# 6_Power.net
KiCad netlist of a schematic drawn in Altium Designer
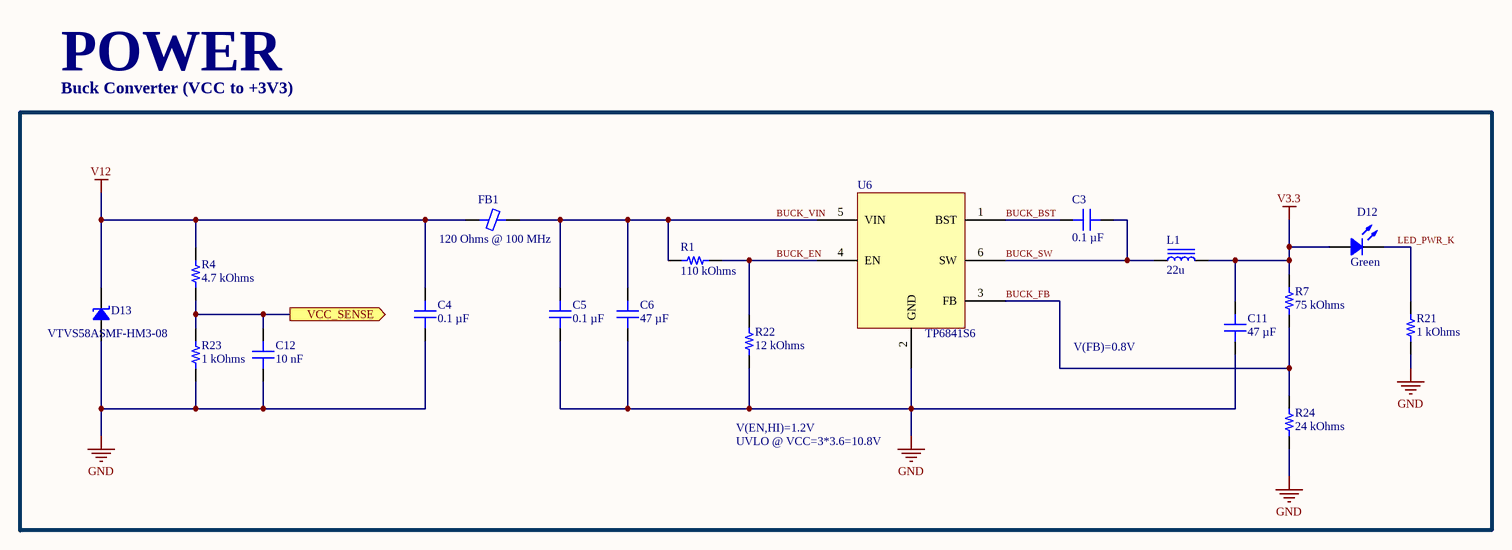
[diagram p0: 6_Power.SchDoc]

(export (version "E")
  (design (tool "Eeschema 10.0.6"))
  (components
    (comp (ref "C3")
      (value "0.1 µF")
      (footprint "CAP 0805_2012")
      (description "CAP CER 0.1UF 50V X7R 0805")
      (fields (field (name "PART NUMBER") "CC0805MRX7R9BB104") (field (name "MANUFACTURER") "Yageo"))
      (libsource (lib "Celestial Altium Library - altium_library") (part "Capacitor"))
    )
    (comp (ref "C4")
      (value "0.1 µF")
      (footprint "CAP 0805_2012")
      (description "CAP CER 0.1UF 50V X7R 0805")
      (fields (field (name "PART NUMBER") "CC0805MRX7R9BB104") (field (name "MANUFACTURER") "Yageo"))
      (libsource (lib "Celestial Altium Library - altium_library") (part "Capacitor"))
    )
    (comp (ref "C5")
      (value "0.1 µF")
      (footprint "CAP 0805_2012")
      (description "CAP CER 0.1UF 50V X7R 0805")
      (fields (field (name "PART NUMBER") "CC0805MRX7R9BB104") (field (name "MANUFACTURER") "Yageo"))
      (libsource (lib "Celestial Altium Library - altium_library") (part "Capacitor"))
    )
    (comp (ref "C6")
      (value "47 µF")
      (footprint "CAP 1210_3225 - 1MM")
      (description "CAP CER 47UF 16V X6S 1210")
      (fields
        (field (name "PART NUMBER") "GRM32EC81C476KE15L")
        (field (name "MANUFACTURER") "Murata Electronics")
      )
      (libsource (lib "Celestial Altium Library - altium_library") (part "Capacitor"))
    )
    (comp (ref "C11")
      (value "47 µF")
      (footprint "CAP 1210_3225 - 1MM")
      (description "CAP CER 47UF 16V X6S 1210")
      (fields
        (field (name "PART NUMBER") "GRM32EC81C476KE15L")
        (field (name "MANUFACTURER") "Murata Electronics")
      )
      (libsource (lib "Celestial Altium Library - altium_library") (part "Capacitor"))
    )
    (comp (ref "C12")
      (value "10 nF")
      (footprint "CAP 0805_2012")
      (description "CAP CER 0805 10NF 100V X7R")
      (fields (field (name "PART NUMBER") "C0805X103K1RAC3316") (field (name "MANUFACTURER") "KEMET"))
      (libsource (lib "Celestial Altium Library - altium_library") (part "Capacitor"))
    )
    (comp (ref "D12")
      (value "Green")
      (footprint "LED 0805_2012 GREEN")
      (description "LED GREEN CLEAR 0805 SMD")
      (fields (field (name "PART NUMBER") "SM0805UGC") (field (name "MANUFACTURER") "Bivar Inc."))
      (libsource (lib "Celestial Altium Library - altium_library") (part "LED"))
    )
    (comp (ref "D13")
      (value "VTVS58ASMF-HM3-08")
      (footprint "SMF DO-219AB")
      (description "TVS DIODE 57.6V 98V DO219AB")
      (fields (field (name "MANUFACTURER") "Vishay Semiconductor Diodes Division"))
      (libsource (lib "Celestial Altium Library - altium_library") (part "DIODE TVS UNI"))
    )
    (comp (ref "FB1")
      (value "120 Ohms @ 100 MHz")
      (footprint "CAP 1812_4532 1.1MM")
      (description "SMT Ferrite Chip")
      (libsource (lib "BLDC_BridgeBoard_V1_2") (part "Ferrite Chip 1812"))
    )
    (comp (ref "L1")
      (value "22u")
      (footprint "Milibreria:INDUCTOR_1R5")
      (description "SMT Inductor")
      (libsource (lib "BLDC_BridgeBoard_V1") (part "Inductor"))
    )
    (comp (ref "R1")
      (value "110 kOhms")
      (footprint "RES 0805_2012")
      (description "RES SMD 110K OHM 1% 1/8W 0805")
      (fields (field (name "PART NUMBER") "CRCW0805110KFKEA") (field (name "MANUFACTURER") "Vishay Dale"))
      (libsource (lib "Celestial Altium Library - altium_library") (part "Resistor"))
    )
    (comp (ref "R4")
      (value "4.7 kOhms")
      (footprint "RES 0805_2012")
      (description "RES SMD 4.7K OHM 5% 1/2W 0805")
      (fields (field (name "PART NUMBER") "RCS08054K70JNEA") (field (name "MANUFACTURER") "Vishay Dale"))
      (libsource (lib "Celestial Altium Library - altium_library") (part "Resistor"))
    )
    (comp (ref "R7")
      (value "75 kOhms")
      (footprint "RES 0805_2012")
      (description "RES SMD 75K OHM 0.5% 1/8W 0805")
      (fields (field (name "PART NUMBER") "RT0805DRD0775KL") (field (name "MANUFACTURER") "Yageo"))
      (libsource (lib "Celestial Altium Library - altium_library") (part "Resistor"))
    )
    (comp (ref "R21")
      (value "1 kOhms")
      (footprint "RES 0805_2012")
      (description "RES SMD 200K OHM 5% 1/8W 0805")
      (fields (field (name "PART NUMBER") "CR0805-JW-204ELF") (field (name "MANUFACTURER") "Bourns Inc."))
      (libsource (lib "Celestial Altium Library - altium_library") (part "Resistor"))
    )
    (comp (ref "R22")
      (value "12 kOhms")
      (footprint "RES 0805_2012")
      (description "RES 12K OHM 1% 1/3W 0805")
      (fields
        (field (name "PART NUMBER") "CRGP0805F12K")
        (field (name "MANUFACTURER") "TE Connectivity Passive Product")
      )
      (libsource (lib "Celestial Altium Library - altium_library") (part "Resistor"))
    )
    (comp (ref "R23")
      (value "1 kOhms")
      (footprint "RES 0805_2012")
      (description "RES SMD 200K OHM 5% 1/8W 0805")
      (fields (field (name "PART NUMBER") "CR0805-JW-204ELF") (field (name "MANUFACTURER") "Bourns Inc."))
      (libsource (lib "Celestial Altium Library - altium_library") (part "Resistor"))
    )
    (comp (ref "R24")
      (value "24 kOhms")
      (footprint "RES 0805_2012")
      (description "RES SMD 24K OHM 1% 1/8W 0805")
      (fields
        (field (name "PART NUMBER") "CRG0805F24K")
        (field (name "MANUFACTURER") "TE Connectivity Passive Product")
      )
      (libsource (lib "Celestial Altium Library - altium_library") (part "Resistor"))
    )
    (comp (ref "U6")
      (value "TP6841S6")
      (footprint "SOT95P280X125-6M")
      (description "TP6841S6 Power Supply. 4.5 to 40 V input voltage. Up to 800 mA output current.")
      (libsource (lib "BLDC_BridgeBoard_V1") (part "TP6841S6"))
    )
  )
  (nets
    (net (code "1") (name "/BUCK_BST") (class "Default")
      (node (ref "C3") (pin "2") (pinfunction "2_2") (pintype "passive"))
      (node (ref "U6") (pin "1") (pinfunction "BST_1") (pintype "passive"))
    )
    (net (code "2") (name "/BUCK_EN") (class "Default")
      (node (ref "R1") (pin "1") (pinfunction "1_1") (pintype "passive"))
      (node (ref "R22") (pin "2") (pinfunction "2_2") (pintype "passive"))
      (node (ref "U6") (pin "4") (pinfunction "EN_4") (pintype "passive"))
    )
    (net (code "3") (name "/BUCK_FB") (class "Default")
      (node (ref "R24") (pin "2") (pinfunction "2_2") (pintype "passive"))
      (node (ref "R7") (pin "1") (pinfunction "1_1") (pintype "passive"))
      (node (ref "U6") (pin "3") (pinfunction "FB_3") (pintype "passive"))
    )
    (net (code "4") (name "/BUCK_SW") (class "Default")
      (node (ref "C3") (pin "1") (pinfunction "1_1") (pintype "passive"))
      (node (ref "L1") (pin "1") (pinfunction "1_1") (pintype "passive"))
      (node (ref "U6") (pin "6") (pinfunction "SW_6") (pintype "passive"))
    )
    (net (code "5") (name "/BUCK_VIN") (class "Default")
      (node (ref "C5") (pin "2") (pinfunction "2_2") (pintype "passive"))
      (node (ref "C6") (pin "2") (pinfunction "2_2") (pintype "passive"))
      (node (ref "FB1") (pin "2") (pinfunction "2_2") (pintype "passive"))
      (node (ref "R1") (pin "2") (pinfunction "2_2") (pintype "passive"))
      (node (ref "U6") (pin "5") (pinfunction "VIN_5") (pintype "passive"))
    )
    (net (code "6") (name "/LED_PWR_K") (class "Default")
      (node (ref "D12") (pin "2") (pinfunction "2_2") (pintype "passive"))
      (node (ref "R21") (pin "2") (pinfunction "2_2") (pintype "passive"))
    )
    (net (code "7") (name "/VCC_SENSE") (class "Default")
      (node (ref "C12") (pin "2") (pinfunction "2_2") (pintype "passive"))
      (node (ref "R23") (pin "2") (pinfunction "2_2") (pintype "passive"))
      (node (ref "R4") (pin "1") (pinfunction "1_1") (pintype "passive"))
    )
    (net (code "8") (name "GND") (class "Default")
      (node (ref "C11") (pin "1") (pinfunction "1_1") (pintype "passive"))
      (node (ref "C12") (pin "1") (pinfunction "1_1") (pintype "passive"))
      (node (ref "C4") (pin "1") (pinfunction "1_1") (pintype "passive"))
      (node (ref "C5") (pin "1") (pinfunction "1_1") (pintype "passive"))
      (node (ref "C6") (pin "1") (pinfunction "1_1") (pintype "passive"))
      (node (ref "D13") (pin "1") (pinfunction "1_1") (pintype "passive"))
      (node (ref "R21") (pin "1") (pinfunction "1_1") (pintype "passive"))
      (node (ref "R22") (pin "1") (pinfunction "1_1") (pintype "passive"))
      (node (ref "R23") (pin "1") (pinfunction "1_1") (pintype "passive"))
      (node (ref "R24") (pin "1") (pinfunction "1_1") (pintype "passive"))
      (node (ref "U6") (pin "2") (pinfunction "GND_2") (pintype "passive"))
    )
    (net (code "9") (name "V3.3") (class "Default")
      (node (ref "C11") (pin "2") (pinfunction "2_2") (pintype "passive"))
      (node (ref "D12") (pin "1") (pinfunction "1_1") (pintype "passive"))
      (node (ref "L1") (pin "2") (pinfunction "2_2") (pintype "passive"))
      (node (ref "R7") (pin "2") (pinfunction "2_2") (pintype "passive"))
    )
    (net (code "10") (name "V12") (class "Default")
      (node (ref "C4") (pin "2") (pinfunction "2_2") (pintype "passive"))
      (node (ref "D13") (pin "2") (pinfunction "2_2") (pintype "passive"))
      (node (ref "FB1") (pin "1") (pinfunction "1_1") (pintype "passive"))
      (node (ref "R4") (pin "2") (pinfunction "2_2") (pintype "passive"))
    )
  )
)
